# CPU.net
KiCad netlist of a schematic drawn in Altium Designer
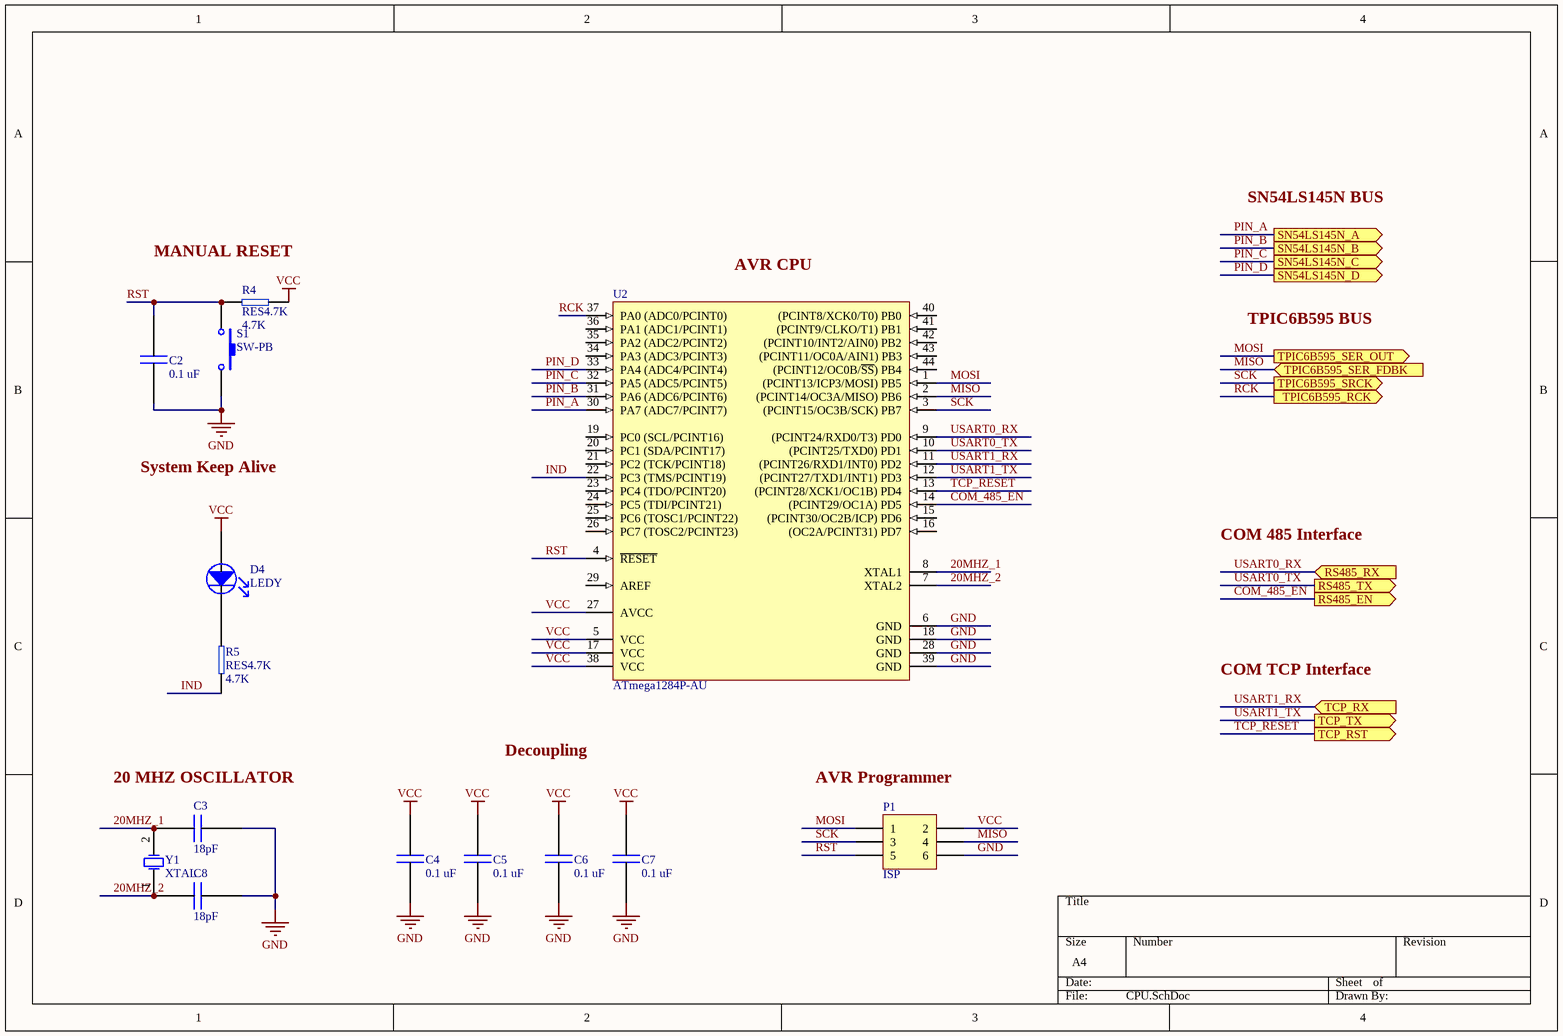
[diagram p0: CPU.SchDoc]

(export (version "E")
  (design (tool "Eeschema 10.0.6"))
  (components
    (comp (ref "C2")
      (value "0.1 uF")
      (footprint "techdev:CAP0603")
      (description "Capacitores cerámicos de capas múltiples (MLCC) - SMD/SMT 0603 0.1uF 16volts X7R 5%")
      (fields (field (name "MPN") "VJ0603Y104JXJPW1BC") (field (name "Comment") "CAP0.1uF"))
      (libsource (lib "Miscellaneous Devices") (part "C0.1UF"))
    )
    (comp (ref "C3")
      (value "18pF")
      (footprint "CAP0603")
      (description "Capacitores cerámicos de capas múltiples (MLCC) - SMD/SMT 0603 18pF 50volts C0G 5%")
      (fields (field (name "MPN") "GRM1885C1H180JA01D") (field (name "Comment") "CAP18pF"))
      (libsource (lib "Miscellaneous Devices") (part "CAP18pF"))
    )
    (comp (ref "C4")
      (value "0.1 uF")
      (footprint "techdev:CAP0603")
      (description "Capacitores cerámicos de capas múltiples (MLCC) - SMD/SMT 0603 0.1uF 16volts X7R 5%")
      (fields (field (name "MPN") "VJ0603Y104JXJPW1BC") (field (name "Comment") "CAP0.1uF"))
      (libsource (lib "Miscellaneous Devices") (part "C0.1UF"))
    )
    (comp (ref "C5")
      (value "0.1 uF")
      (footprint "techdev:CAP0603")
      (description "Capacitores cerámicos de capas múltiples (MLCC) - SMD/SMT 0603 0.1uF 16volts X7R 5%")
      (fields (field (name "MPN") "VJ0603Y104JXJPW1BC") (field (name "Comment") "CAP0.1uF"))
      (libsource (lib "Miscellaneous Devices") (part "C0.1UF"))
    )
    (comp (ref "C6")
      (value "0.1 uF")
      (footprint "techdev:CAP0603")
      (description "Capacitores cerámicos de capas múltiples (MLCC) - SMD/SMT 0603 0.1uF 16volts X7R 5%")
      (fields (field (name "MPN") "VJ0603Y104JXJPW1BC") (field (name "Comment") "CAP0.1uF"))
      (libsource (lib "Miscellaneous Devices") (part "C0.1UF"))
    )
    (comp (ref "C7")
      (value "0.1 uF")
      (footprint "techdev:CAP0603")
      (description "Capacitores cerámicos de capas múltiples (MLCC) - SMD/SMT 0603 0.1uF 16volts X7R 5%")
      (fields (field (name "MPN") "VJ0603Y104JXJPW1BC") (field (name "Comment") "CAP0.1uF"))
      (libsource (lib "Miscellaneous Devices") (part "C0.1UF"))
    )
    (comp (ref "C8")
      (value "18pF")
      (footprint "CAP0603")
      (description "Capacitores cerámicos de capas múltiples (MLCC) - SMD/SMT 0603 18pF 50volts C0G 5%")
      (fields (field (name "MPN") "GRM1885C1H180JA01D") (field (name "Comment") "CAP18pF"))
      (libsource (lib "Miscellaneous Devices") (part "CAP18pF"))
    )
    (comp (ref "D4")
      (value "LEDY")
      (footprint "150060YS75000")
      (description "LED estándar - SMD (montaje superficial) WL-SMCW SMDMono TpVw Waterclr 0603 Yellow")
      (fields (field (name "MPN") "150060YS75000"))
      (libsource (lib "techdev") (part "LEDY"))
    )
    (comp (ref "P1")
      (value "ISP")
      (footprint "HDR2X3")
      (description "Alojamientos de cables y cabecera 2X03P DUAL ROW")
      (fields (field (name "MPN") "826925-3"))
      (libsource (lib "Miscellaneous Connectors") (part "Header 3X2"))
    )
    (comp (ref "R4")
      (value "RES4.7K")
      (footprint "RES0603")
      (description "Resistores de película gruesa - SMD 1/10watt 4.7Kohms 1%")
      (fields (field (name "MPN") "CRCW06034K70FKEA") (field (name "ALTIUM_VALUE") "4.7K"))
      (libsource (lib "") (part "RES4.7K_1"))
    )
    (comp (ref "R5")
      (value "RES4.7K")
      (footprint "RES0603")
      (description "Resistores de película gruesa - SMD 1/10watt 4.7Kohms 1%")
      (fields (field (name "MPN") "CRCW06034K70FKEA") (field (name "ALTIUM_VALUE") "4.7K"))
      (libsource (lib "Miscellaneous Devices") (part "RES4.7K"))
    )
    (comp (ref "S1")
      (value "SW-PB")
      (footprint "techdev:microswitch")
      (description "Switch")
      (fields (field (name "MPN") "PTS635SL43SMTR LFS"))
      (libsource (lib "Miscellaneous Devices") (part "SW-PB"))
    )
    (comp (ref "U2")
      (value "ATmega1284P-AU")
      (footprint "44A_N")
      (description "20 MHz 8-bit AVR Microcontroller with 128KB Flash, 44-Pin TQFP Pkg, Industrial Temp")
      (fields (field (name "MPN") "ATMEGA1284P-AU"))
      (libsource (lib "Atmel Communication ICs") (part "ATmega1284P-AU"))
    )
    (comp (ref "Y1")
      (value "XTAL")
      (footprint "techdev:Crystal20MHz")
      (description "Cristales 20MHz 16pF -10C +70C")
      (fields (field (name "MPN") "ECS-200-16-5PX-TR"))
      (libsource (lib "Miscellaneous Devices") (part "XTAL"))
    )
  )
  (nets
    (net (code "2") (name "/20MHZ_1") (class "Default")
      (node (ref "C3") (pin "1") (pintype "passive"))
      (node (ref "U2") (pin "8") (pinfunction "XTAL1_8") (pintype "passive"))
      (node (ref "Y1") (pin "2") (pinfunction "OSC2_2") (pintype "passive"))
    )
    (net (code "3") (name "/20MHZ_2") (class "Default")
      (node (ref "C8") (pin "1") (pintype "passive"))
      (node (ref "U2") (pin "7") (pinfunction "XTAL2_7") (pintype "passive"))
      (node (ref "Y1") (pin "1") (pinfunction "OSC1_1") (pintype "passive"))
    )
    (net (code "8") (name "/COM_485_EN") (class "Default")
      (node (ref "U2") (pin "14") (pinfunction "(PCINT29/OC1A)_PD5_14") (pintype "input"))
    )
    (net (code "10") (name "/IND") (class "Default")
      (node (ref "R5") (pin "1") (pinfunction "pos_1") (pintype "passive"))
      (node (ref "U2") (pin "22") (pinfunction "PC3_(TMS/PCINT19)_22") (pintype "input"))
    )
    (net (code "12") (name "/MISO") (class "Default")
      (node (ref "P1") (pin "4") (pinfunction "4_4") (pintype "passive"))
      (node (ref "U2") (pin "2") (pinfunction "(PCINT14/OC3A/MISO)_PB6_2") (pintype "input"))
    )
    (net (code "13") (name "/MOSI") (class "Default")
      (node (ref "P1") (pin "1") (pinfunction "1_1") (pintype "passive"))
      (node (ref "U2") (pin "1") (pinfunction "(PCINT13/ICP3/MOSI)_PB5_1") (pintype "input"))
    )
    (net (code "14") (name "/PIN_A") (class "Default")
      (node (ref "U2") (pin "30") (pinfunction "PA7_(ADC7/PCINT7)_30") (pintype "input"))
    )
    (net (code "15") (name "/PIN_B") (class "Default")
      (node (ref "U2") (pin "31") (pinfunction "PA6_(ADC6/PCINT6)_31") (pintype "input"))
    )
    (net (code "16") (name "/PIN_C") (class "Default")
      (node (ref "U2") (pin "32") (pinfunction "PA5_(ADC5/PCINT5)_32") (pintype "input"))
    )
    (net (code "17") (name "/PIN_D") (class "Default")
      (node (ref "U2") (pin "33") (pinfunction "PA4_(ADC4/PCINT4)_33") (pintype "input"))
    )
    (net (code "18") (name "/RCK") (class "Default")
      (node (ref "U2") (pin "37") (pinfunction "PA0_(ADC0/PCINT0)_37") (pintype "input"))
    )
    (net (code "19") (name "/RST") (class "Default")
      (node (ref "C2") (pin "1") (pintype "passive"))
      (node (ref "P1") (pin "5") (pinfunction "5_5") (pintype "passive"))
      (node (ref "R4") (pin "1") (pinfunction "pos_1") (pintype "passive"))
      (node (ref "S1") (pin "1") (pinfunction "1_1") (pintype "passive"))
      (node (ref "U2") (pin "4") (pinfunction "~{RESET}_4") (pintype "input"))
    )
    (net (code "20") (name "/SCK") (class "Default")
      (node (ref "P1") (pin "3") (pinfunction "3_3") (pintype "passive"))
      (node (ref "U2") (pin "3") (pinfunction "(PCINT15/OC3B/SCK)_PB7_3") (pintype "input"))
    )
    (net (code "23") (name "/TCP_RESET") (class "Default")
      (node (ref "U2") (pin "13") (pinfunction "(PCINT28/XCK1/OC1B)_PD4_13") (pintype "input"))
    )
    (net (code "25") (name "/USART0_RX") (class "Default")
      (node (ref "U2") (pin "9") (pinfunction "(PCINT24/RXD0/T3)_PD0_9") (pintype "input"))
    )
    (net (code "26") (name "/USART0_TX") (class "Default")
      (node (ref "U2") (pin "10") (pinfunction "(PCINT25/TXD0)_PD1_10") (pintype "input"))
    )
    (net (code "27") (name "/USART1_RX") (class "Default")
      (node (ref "U2") (pin "11") (pinfunction "(PCINT26/RXD1/INT0)_PD2_11") (pintype "input"))
    )
    (net (code "28") (name "/USART1_TX") (class "Default")
      (node (ref "U2") (pin "12") (pinfunction "(PCINT27/TXD1/INT1)_PD3_12") (pintype "input"))
    )
    (net (code "29") (name "GND") (class "Default")
      (node (ref "C2") (pin "2") (pintype "passive"))
      (node (ref "C3") (pin "2") (pintype "passive"))
      (node (ref "C4") (pin "2") (pintype "passive"))
      (node (ref "C5") (pin "2") (pintype "passive"))
      (node (ref "C6") (pin "2") (pintype "passive"))
      (node (ref "C7") (pin "2") (pintype "passive"))
      (node (ref "C8") (pin "2") (pintype "passive"))
      (node (ref "P1") (pin "6") (pinfunction "6_6") (pintype "passive"))
      (node (ref "S1") (pin "2") (pinfunction "2_2") (pintype "passive"))
      (node (ref "U2") (pin "18") (pinfunction "GND_18") (pintype "passive"))
      (node (ref "U2") (pin "28") (pinfunction "GND_28") (pintype "passive"))
      (node (ref "U2") (pin "39") (pinfunction "GND_39") (pintype "passive"))
      (node (ref "U2") (pin "6") (pinfunction "GND_6") (pintype "passive"))
    )
    (net (code "30") (name "Net-(D4-Cathode)") (class "Default")
      (node (ref "D4") (pin "1") (pinfunction "Cathode_1") (pintype "passive"))
      (node (ref "R5") (pin "2") (pinfunction "neg_2") (pintype "passive"))
    )
    (net (code "31") (name "VCC") (class "Default")
      (node (ref "C4") (pin "1") (pintype "passive"))
      (node (ref "C5") (pin "1") (pintype "passive"))
      (node (ref "C6") (pin "1") (pintype "passive"))
      (node (ref "C7") (pin "1") (pintype "passive"))
      (node (ref "D4") (pin "2") (pinfunction "Anode_2") (pintype "passive"))
      (node (ref "P1") (pin "2") (pinfunction "2_2") (pintype "passive"))
      (node (ref "R4") (pin "2") (pinfunction "neg_2") (pintype "passive"))
      (node (ref "U2") (pin "17") (pinfunction "VCC_17") (pintype "passive"))
      (node (ref "U2") (pin "27") (pinfunction "AVCC_27") (pintype "passive"))
      (node (ref "U2") (pin "38") (pinfunction "VCC_38") (pintype "passive"))
      (node (ref "U2") (pin "5") (pinfunction "VCC_5") (pintype "passive"))
    )
    (net (code "32") (name "unconnected-(U2-(OC2A{slash}PCINT31)_PD7-Pad16)") (class "Default")
      (node (ref "U2") (pin "16") (pinfunction "(OC2A/PCINT31)_PD7_16") (pintype "input"))
    )
    (net (code "33") (name "unconnected-(U2-(PCINT8{slash}XCK0{slash}T0)_PB0-Pad40)") (class "Default")
      (node (ref "U2") (pin "40") (pinfunction "(PCINT8/XCK0/T0)_PB0_40") (pintype "input"))
    )
    (net (code "34") (name "unconnected-(U2-(PCINT9{slash}CLKO{slash}T1)_PB1-Pad41)") (class "Default")
      (node (ref "U2") (pin "41") (pinfunction "(PCINT9/CLKO/T1)_PB1_41") (pintype "input"))
    )
    (net (code "35") (name "unconnected-(U2-(PCINT10{slash}INT2{slash}AIN0)_PB2-Pad42)") (class "Default")
      (node (ref "U2") (pin "42") (pinfunction "(PCINT10/INT2/AIN0)_PB2_42") (pintype "input"))
    )
    (net (code "36") (name "unconnected-(U2-(PCINT11{slash}OC0A{slash}AIN1)_PB3-Pad43)") (class "Default")
      (node (ref "U2") (pin "43") (pinfunction "(PCINT11/OC0A/AIN1)_PB3_43") (pintype "input"))
    )
    (net (code "37") (name "unconnected-(U2-(PCINT12{slash}OC0B{slash}~{SS})_PB4-Pad44)") (class "Default")
      (node (ref "U2") (pin "44") (pinfunction "(PCINT12/OC0B/~{SS})_PB4_44") (pintype "input"))
    )
    (net (code "38") (name "unconnected-(U2-(PCINT30{slash}OC2B{slash}ICP)_PD6-Pad15)") (class "Default")
      (node (ref "U2") (pin "15") (pinfunction "(PCINT30/OC2B/ICP)_PD6_15") (pintype "input"))
    )
    (net (code "39") (name "unconnected-(U2-AREF-Pad29)") (class "Default")
      (node (ref "U2") (pin "29") (pinfunction "AREF_29") (pintype "input"))
    )
    (net (code "40") (name "unconnected-(U2-PA1_(ADC1{slash}PCINT1)-Pad36)") (class "Default")
      (node (ref "U2") (pin "36") (pinfunction "PA1_(ADC1/PCINT1)_36") (pintype "input"))
    )
    (net (code "41") (name "unconnected-(U2-PA2_(ADC2{slash}PCINT2)-Pad35)") (class "Default")
      (node (ref "U2") (pin "35") (pinfunction "PA2_(ADC2/PCINT2)_35") (pintype "input"))
    )
    (net (code "42") (name "unconnected-(U2-PA3_(ADC3{slash}PCINT3)-Pad34)") (class "Default")
      (node (ref "U2") (pin "34") (pinfunction "PA3_(ADC3/PCINT3)_34") (pintype "input"))
    )
    (net (code "43") (name "unconnected-(U2-PC0_(SCL{slash}PCINT16)-Pad19)") (class "Default")
      (node (ref "U2") (pin "19") (pinfunction "PC0_(SCL/PCINT16)_19") (pintype "input"))
    )
    (net (code "44") (name "unconnected-(U2-PC1_(SDA{slash}PCINT17)-Pad20)") (class "Default")
      (node (ref "U2") (pin "20") (pinfunction "PC1_(SDA/PCINT17)_20") (pintype "input"))
    )
    (net (code "45") (name "unconnected-(U2-PC2_(TCK{slash}PCINT18)-Pad21)") (class "Default")
      (node (ref "U2") (pin "21") (pinfunction "PC2_(TCK/PCINT18)_21") (pintype "input"))
    )
    (net (code "46") (name "unconnected-(U2-PC4_(TDO{slash}PCINT20)-Pad23)") (class "Default")
      (node (ref "U2") (pin "23") (pinfunction "PC4_(TDO/PCINT20)_23") (pintype "input"))
    )
    (net (code "47") (name "unconnected-(U2-PC5_(TDI{slash}PCINT21)-Pad24)") (class "Default")
      (node (ref "U2") (pin "24") (pinfunction "PC5_(TDI/PCINT21)_24") (pintype "input"))
    )
    (net (code "48") (name "unconnected-(U2-PC6_(TOSC1{slash}PCINT22)-Pad25)") (class "Default")
      (node (ref "U2") (pin "25") (pinfunction "PC6_(TOSC1/PCINT22)_25") (pintype "input"))
    )
    (net (code "49") (name "unconnected-(U2-PC7_(TOSC2{slash}PCINT23)-Pad26)") (class "Default")
      (node (ref "U2") (pin "26") (pinfunction "PC7_(TOSC2/PCINT23)_26") (pintype "input"))
    )
  )
)
